# obc_main.net
KiCad netlist of a schematic drawn in Altium Designer
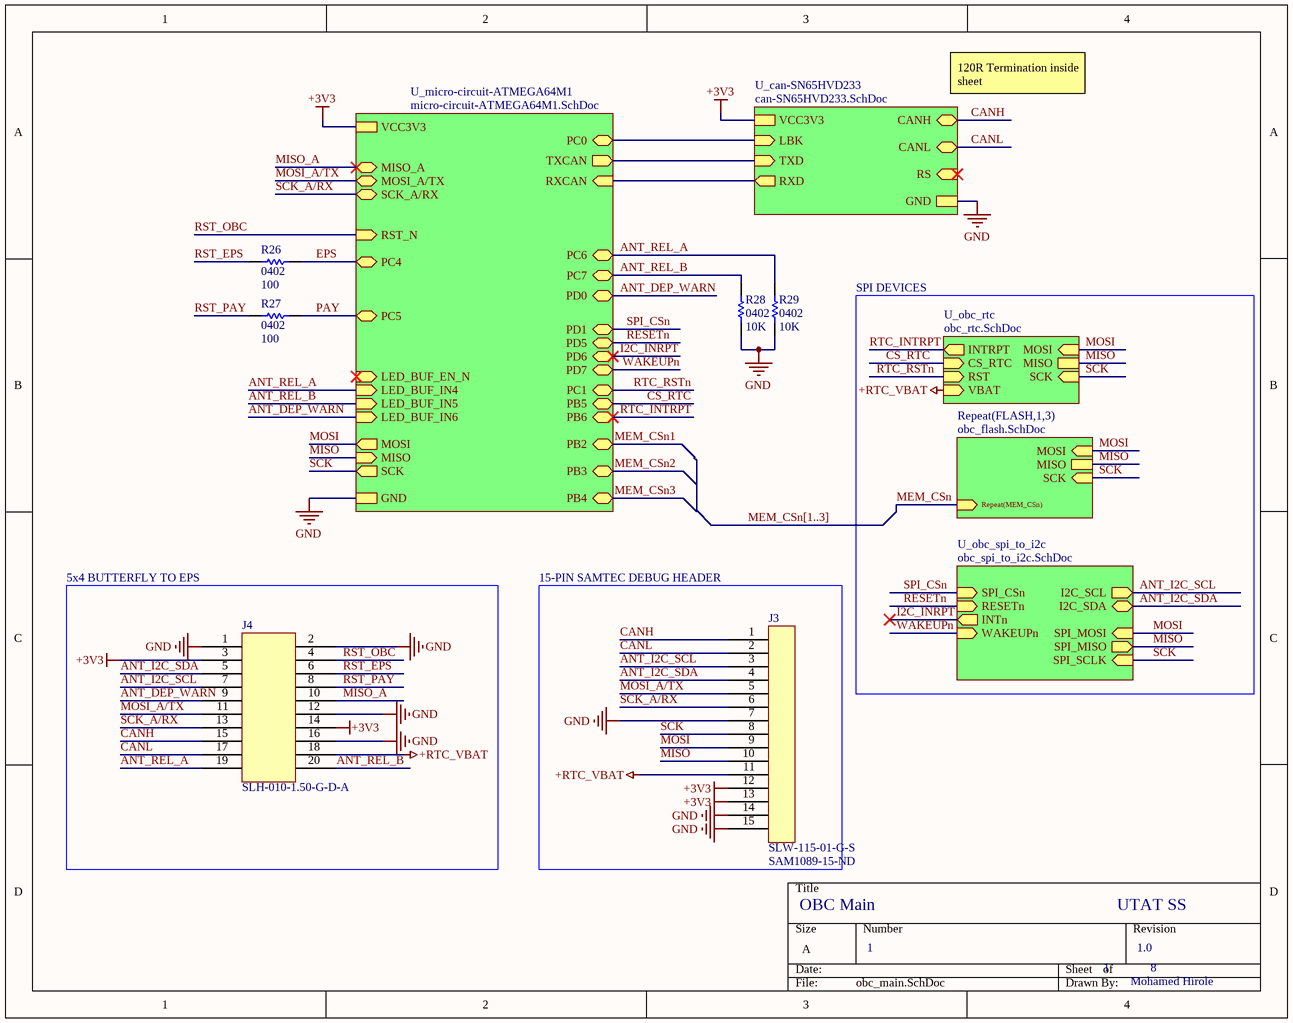
[diagram p0: obc_main.SchDoc]

(export (version "E")
  (design (tool "Eeschema 10.0.6"))
  (components
    (comp (ref "J3")
      (value "SLW-115-01-G-S")
      (footprint "SAM1089-15-ND")
      (description "15 Position Receptacle Connector 0.100\" (2.54mm) Through Hole Gold")
      (fields (field (name "MANUFACTURER") "Samtec") (field (name "SUPPLIER PART NUMBER 1") "SAM1089-15-ND"))
      (libsource (lib "heron-general") (part "SLW-115-01-G-S"))
    )
    (comp (ref "J4")
      (value "SLH-010-1.50-G-D-A")
      (footprint "SLH-010-1.50-G-D-A")
      (description "0.50 mm Razor Beam™ LP Ultra Low Profile Socket Strip, alignment pin option")
      (libsource (lib "heron-general") (part "SLH-010-1.50-G-D-A"))
    )
    (comp (ref "R26")
      (value "0402")
      (footprint "RES0402R")
      (description "0402 resistor")
      (fields (field (name "ALTIUM_VALUE") "100"))
      (libsource (lib "heron-general") (part "RES0402"))
    )
    (comp (ref "R27")
      (value "0402")
      (footprint "RES0402R")
      (description "0402 resistor")
      (fields (field (name "ALTIUM_VALUE") "100"))
      (libsource (lib "heron-general") (part "RES0402"))
    )
    (comp (ref "R28")
      (value "0402")
      (footprint "RES0402R")
      (description "0402 resistor")
      (fields (field (name "ALTIUM_VALUE") "10K"))
      (libsource (lib "heron-general") (part "RES0402"))
    )
    (comp (ref "R29")
      (value "0402")
      (footprint "RES0402R")
      (description "0402 resistor")
      (fields (field (name "ALTIUM_VALUE") "10K"))
      (libsource (lib "heron-general") (part "RES0402"))
    )
  )
  (nets
    (net (code "1") (name "+3V3") (class "Default")
      (node (ref "J3") (pin "12") (pintype "passive"))
      (node (ref "J3") (pin "13") (pintype "passive"))
      (node (ref "J4") (pin "14") (pintype "passive"))
      (node (ref "J4") (pin "3") (pintype "passive"))
    )
    (net (code "2") (name "+RTC_VBAT") (class "Default")
      (node (ref "J3") (pin "11") (pintype "passive"))
      (node (ref "J4") (pin "18") (pintype "passive"))
    )
    (net (code "3") (name "/ANT_DEP_WARN") (class "Default") (node (ref "J4") (pin "9") (pintype "passive")))
    (net (code "4") (name "/ANT_I2C_SCL") (class "Default")
      (node (ref "J3") (pin "3") (pintype "passive"))
      (node (ref "J4") (pin "7") (pintype "passive"))
    )
    (net (code "5") (name "/ANT_I2C_SDA") (class "Default")
      (node (ref "J3") (pin "4") (pintype "passive"))
      (node (ref "J4") (pin "5") (pintype "passive"))
    )
    (net (code "6") (name "/ANT_REL_A") (class "Default")
      (node (ref "J4") (pin "19") (pintype "passive"))
      (node (ref "R29") (pin "2") (pinfunction "2_2") (pintype "passive"))
    )
    (net (code "7") (name "/ANT_REL_B") (class "Default")
      (node (ref "J4") (pin "20") (pintype "passive"))
      (node (ref "R28") (pin "2") (pinfunction "2_2") (pintype "passive"))
    )
    (net (code "8") (name "/CANH") (class "Default")
      (node (ref "J3") (pin "1") (pintype "passive"))
      (node (ref "J4") (pin "15") (pintype "passive"))
    )
    (net (code "9") (name "/CANL") (class "Default")
      (node (ref "J3") (pin "2") (pintype "passive"))
      (node (ref "J4") (pin "17") (pintype "passive"))
    )
    (net (code "11") (name "/EPS") (class "Default")
      (node (ref "R26") (pin "2") (pinfunction "2_2") (pintype "passive"))
    )
    (net (code "20") (name "/MISO") (class "Default") (node (ref "J3") (pin "10") (pintype "passive")))
    (net (code "21") (name "/MISO_A") (class "Default") (node (ref "J4") (pin "10") (pintype "passive")))
    (net (code "22") (name "/MOSI") (class "Default") (node (ref "J3") (pin "9") (pintype "passive")))
    (net (code "23") (name "/MOSI_A{slash}TX") (class "Default")
      (node (ref "J3") (pin "5") (pintype "passive"))
      (node (ref "J4") (pin "11") (pintype "passive"))
    )
    (net (code "24") (name "/PAY") (class "Default")
      (node (ref "R27") (pin "2") (pinfunction "2_2") (pintype "passive"))
    )
    (net (code "27") (name "/RST_EPS") (class "Default")
      (node (ref "J4") (pin "6") (pintype "passive"))
      (node (ref "R26") (pin "1") (pinfunction "1_1") (pintype "passive"))
    )
    (net (code "28") (name "/RST_OBC") (class "Default") (node (ref "J4") (pin "4") (pintype "passive")))
    (net (code "29") (name "/RST_PAY") (class "Default")
      (node (ref "J4") (pin "8") (pintype "passive"))
      (node (ref "R27") (pin "1") (pinfunction "1_1") (pintype "passive"))
    )
    (net (code "33") (name "/SCK") (class "Default") (node (ref "J3") (pin "8") (pintype "passive")))
    (net (code "34") (name "/SCK_A{slash}RX") (class "Default")
      (node (ref "J3") (pin "6") (pintype "passive"))
      (node (ref "J4") (pin "13") (pintype "passive"))
    )
    (net (code "38") (name "GND") (class "Default")
      (node (ref "J3") (pin "14") (pintype "passive"))
      (node (ref "J3") (pin "15") (pintype "passive"))
      (node (ref "J3") (pin "7") (pintype "passive"))
      (node (ref "J4") (pin "1") (pintype "passive"))
      (node (ref "J4") (pin "12") (pintype "passive"))
      (node (ref "J4") (pin "16") (pintype "passive"))
      (node (ref "J4") (pin "2") (pintype "passive"))
      (node (ref "R28") (pin "1") (pinfunction "1_1") (pintype "passive"))
      (node (ref "R29") (pin "1") (pinfunction "1_1") (pintype "passive"))
    )
  )
)
